# analyzer.net
KiCad netlist of a schematic drawn in EAGLE
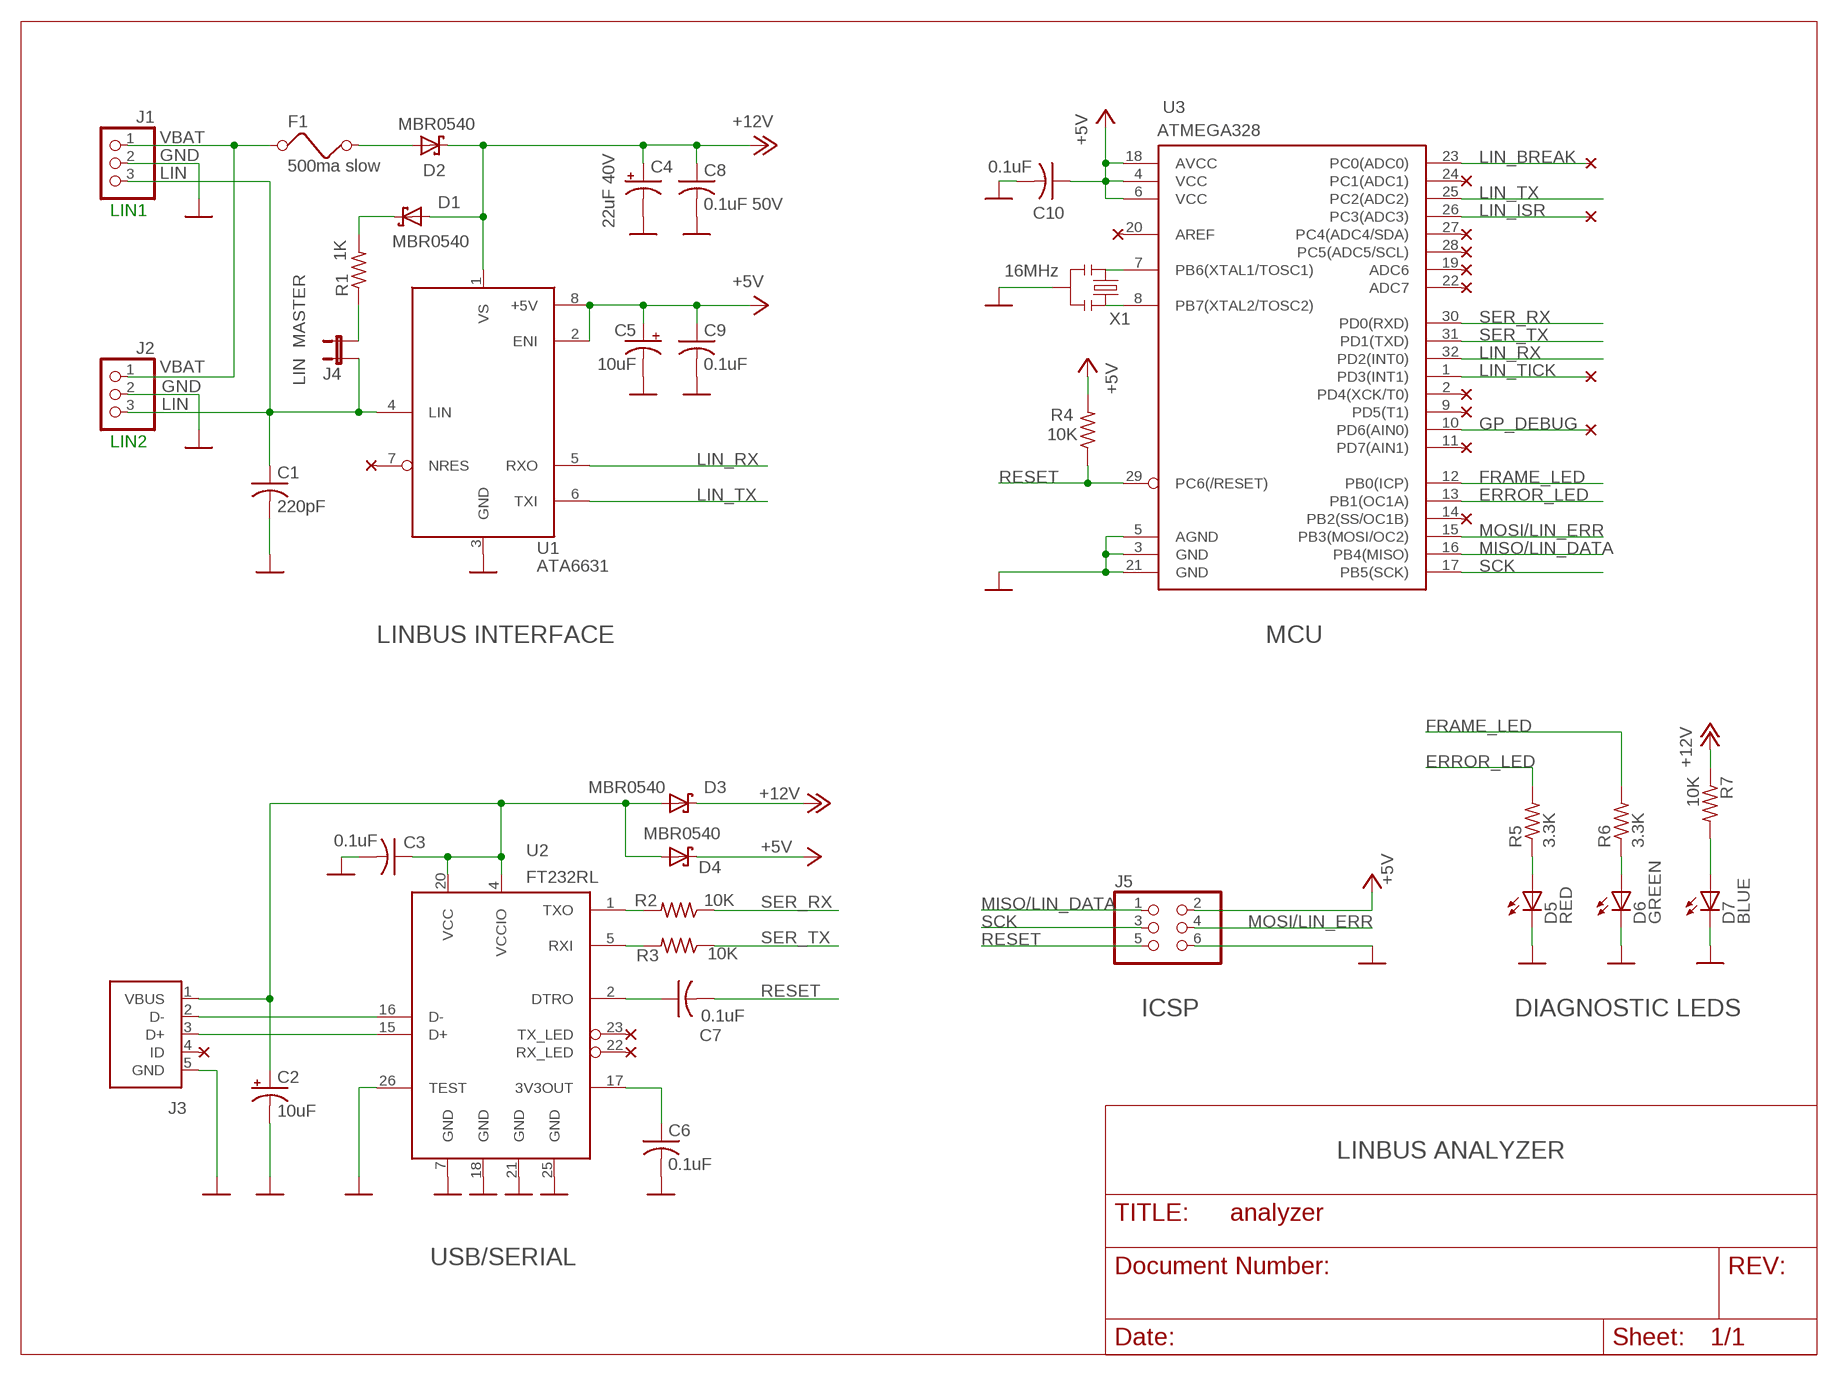
[diagram p0: schematic, sheet 1]

(export (version "E")
  (design (tool "Eeschema 10.0.6"))
  (components
    (comp (ref "C1")
      (value "220pF")
      (footprint "eagle-import:C0805")
      (libsource (lib "eagle-import") (part "C-USC0805"))
    )
    (comp (ref "C2")
      (value "10uF")
      (footprint "eagle-import:A_3216-18R")
      (libsource (lib "eagle-import") (part "CPOL-USA/3216-18R"))
    )
    (comp (ref "C3")
      (value "0.1uF")
      (footprint "eagle-import:C0805")
      (libsource (lib "eagle-import") (part "C-USC0805"))
    )
    (comp (ref "C4")
      (value "22uF 40V")
      (footprint "eagle-import:UD-6,3X5,8_NICHICON")
      (libsource (lib "eagle-import") (part "CPOL-USUD-6,3X5,8"))
    )
    (comp (ref "C5")
      (value "10uF")
      (footprint "eagle-import:A_3216-18R")
      (libsource (lib "eagle-import") (part "CPOL-USA/3216-18R"))
    )
    (comp (ref "C6")
      (value "0.1uF")
      (footprint "eagle-import:C0805")
      (libsource (lib "eagle-import") (part "C-USC0805"))
    )
    (comp (ref "C7")
      (value "0.1uF")
      (footprint "eagle-import:C0805")
      (libsource (lib "eagle-import") (part "C-USC0805"))
    )
    (comp (ref "C8")
      (value "0.1uF 50V")
      (footprint "eagle-import:C0805")
      (libsource (lib "eagle-import") (part "C-USC0805"))
    )
    (comp (ref "C9")
      (value "0.1uF")
      (footprint "eagle-import:C0805")
      (libsource (lib "eagle-import") (part "C-USC0805"))
    )
    (comp (ref "C10")
      (value "0.1uF")
      (footprint "eagle-import:C0805")
      (libsource (lib "eagle-import") (part "C-USC0805"))
    )
    (comp (ref "D1")
      (value "MBR0540")
      (footprint "eagle-import:SOD123FL")
      (libsource (lib "eagle-import") (part "SMF5.0AT1"))
    )
    (comp (ref "D2")
      (value "MBR0540")
      (footprint "eagle-import:SOD123FL")
      (libsource (lib "eagle-import") (part "SMF5.0AT1"))
    )
    (comp (ref "D3")
      (value "MBR0540")
      (footprint "eagle-import:SOD123FL")
      (libsource (lib "eagle-import") (part "SMF5.0AT1"))
    )
    (comp (ref "D4")
      (value "MBR0540")
      (footprint "eagle-import:SOD123FL")
      (libsource (lib "eagle-import") (part "SMF5.0AT1"))
    )
    (comp (ref "D5")
      (value "RED")
      (footprint "eagle-import:1206-LED")
      (libsource (lib "eagle-import") (part "LED"))
    )
    (comp (ref "D6")
      (value "GREEN")
      (footprint "eagle-import:1206-LED")
      (libsource (lib "eagle-import") (part "LED"))
    )
    (comp (ref "D7")
      (value "BLUE")
      (footprint "eagle-import:1206-LED")
      (libsource (lib "eagle-import") (part "LED"))
    )
    (comp (ref "F1")
      (value "500ma slow")
      (footprint "eagle-import:1206")
      (libsource (lib "eagle-import") (part "FUSE"))
    )
    (comp (ref "J1")
      (value "PINHD-1X3")
      (footprint "eagle-import:1X03")
      (libsource (lib "eagle-import") (part "PINHD-1X3"))
    )
    (comp (ref "J2")
      (value "PINHD-1X3")
      (footprint "eagle-import:1X03")
      (libsource (lib "eagle-import") (part "PINHD-1X3"))
    )
    (comp (ref "J3")
      (value "USBSMD")
      (footprint "eagle-import:USB-MINIB")
      (libsource (lib "eagle-import") (part "USBSMD"))
    )
    (comp (ref "J4")
      (value "JP1E")
      (footprint "eagle-import:JP1")
      (libsource (lib "eagle-import") (part "JP1E"))
    )
    (comp (ref "J5")
      (value "PINHD-2X3")
      (footprint "eagle-import:2X03")
      (libsource (lib "eagle-import") (part "PINHD-2X3"))
    )
    (comp (ref "R1")
      (value "1K")
      (footprint "eagle-import:R0805")
      (libsource (lib "eagle-import") (part "R-US_R0805"))
    )
    (comp (ref "R2")
      (value "10K")
      (footprint "eagle-import:R0805")
      (libsource (lib "eagle-import") (part "R-US_R0805"))
    )
    (comp (ref "R3")
      (value "10K")
      (footprint "eagle-import:R0805")
      (libsource (lib "eagle-import") (part "R-US_R0805"))
    )
    (comp (ref "R4")
      (value "10K")
      (footprint "eagle-import:R0805")
      (libsource (lib "eagle-import") (part "R-US_R0805"))
    )
    (comp (ref "R5")
      (value "3.3K")
      (footprint "eagle-import:R0805")
      (libsource (lib "eagle-import") (part "R-US_R0805"))
    )
    (comp (ref "R6")
      (value "3.3K")
      (footprint "eagle-import:R0805")
      (libsource (lib "eagle-import") (part "R-US_R0805"))
    )
    (comp (ref "R7")
      (value "10K")
      (footprint "eagle-import:R0805")
      (libsource (lib "eagle-import") (part "R-US_R0805"))
    )
    (comp (ref "U1")
      (value "ATA6631")
      (footprint "eagle-import:SO-08")
      (libsource (lib "eagle-import") (part "ATA6631"))
    )
    (comp (ref "U2")
      (value "FT232RL")
      (footprint "eagle-import:SSOP28DB")
      (libsource (lib "eagle-import") (part "FT232RL"))
    )
    (comp (ref "U3")
      (value "ATMEGA328")
      (footprint "eagle-import:TQFP32-08")
      (libsource (lib "eagle-import") (part "ATMEGA328"))
    )
    (comp (ref "X1")
      (value "16MHz")
      (footprint "eagle-import:RESONATOR-SMD")
      (libsource (lib "eagle-import") (part "RESONATORSMD"))
    )
  )
  (nets
    (net (code "1") (name "+5V") (class "Default")
      (node (ref "C10") (pin "1") (pinfunction "1_1") (pintype "passive"))
      (node (ref "C5") (pin "+") (pinfunction "+_+") (pintype "passive"))
      (node (ref "C9") (pin "1") (pinfunction "1_1") (pintype "passive"))
      (node (ref "D4") (pin "C") (pinfunction "C_C") (pintype "passive"))
      (node (ref "J5") (pin "2") (pinfunction "2_2") (pintype "passive"))
      (node (ref "R4") (pin "2") (pinfunction "2_2") (pintype "passive"))
      (node (ref "U1") (pin "2") (pinfunction "ENI_2") (pintype "input"))
      (node (ref "U1") (pin "8") (pinfunction "+5V_8") (pintype "power_in"))
      (node (ref "U3") (pin "18") (pinfunction "AVCC_18") (pintype "power_in"))
      (node (ref "U3") (pin "4") (pinfunction "VCC_4") (pintype "power_in"))
      (node (ref "U3") (pin "6") (pinfunction "VCC_6") (pintype "power_in"))
    )
    (net (code "2") (name "+12V") (class "Default")
      (node (ref "C4") (pin "+") (pinfunction "+_+") (pintype "passive"))
      (node (ref "C8") (pin "1") (pinfunction "1_1") (pintype "passive"))
      (node (ref "D1") (pin "A") (pinfunction "A_A") (pintype "passive"))
      (node (ref "D2") (pin "C") (pinfunction "C_C") (pintype "passive"))
      (node (ref "D3") (pin "C") (pinfunction "C_C") (pintype "passive"))
      (node (ref "R7") (pin "1") (pinfunction "1_1") (pintype "passive"))
      (node (ref "U1") (pin "1") (pinfunction "VS_1") (pintype "power_in"))
    )
    (net (code "3") (name "/AREF") (class "Default")
      (node (ref "U3") (pin "20") (pinfunction "AREF_20") (pintype "power_in"))
    )
    (net (code "4") (name "/ERROR_LED") (class "Default")
      (node (ref "R5") (pin "2") (pinfunction "2_2") (pintype "passive"))
      (node (ref "U3") (pin "13") (pinfunction "PB1(OC1A)_13") (pintype "bidirectional"))
    )
    (net (code "5") (name "/FRAME_LED") (class "Default")
      (node (ref "R6") (pin "2") (pinfunction "2_2") (pintype "passive"))
      (node (ref "U3") (pin "12") (pinfunction "PB0(ICP)_12") (pintype "bidirectional"))
    )
    (net (code "6") (name "/GP_DEBUG") (class "Default")
      (node (ref "U3") (pin "10") (pinfunction "PD6(AIN0)_10") (pintype "bidirectional"))
    )
    (net (code "7") (name "/LIN") (class "Default")
      (node (ref "C1") (pin "1") (pinfunction "1_1") (pintype "passive"))
      (node (ref "J1") (pin "3") (pinfunction "3_3") (pintype "passive"))
      (node (ref "J2") (pin "3") (pinfunction "3_3") (pintype "passive"))
      (node (ref "J4") (pin "1") (pinfunction "1_1") (pintype "passive"))
      (node (ref "U1") (pin "4") (pinfunction "LIN_4") (pintype "bidirectional"))
    )
    (net (code "8") (name "/LIN_BREAK") (class "Default")
      (node (ref "U3") (pin "23") (pinfunction "PC0(ADC0)_23") (pintype "bidirectional"))
    )
    (net (code "9") (name "/LIN_ISR") (class "Default")
      (node (ref "U3") (pin "26") (pinfunction "PC3(ADC3)_26") (pintype "bidirectional"))
    )
    (net (code "10") (name "/LIN_RX") (class "Default")
      (node (ref "U1") (pin "5") (pinfunction "RXO_5") (pintype "output"))
      (node (ref "U3") (pin "32") (pinfunction "PD2(INT0)_32") (pintype "bidirectional"))
    )
    (net (code "11") (name "/LIN_TICK") (class "Default")
      (node (ref "U3") (pin "1") (pinfunction "PD3(INT1)_1") (pintype "bidirectional"))
    )
    (net (code "12") (name "/LIN_TX") (class "Default")
      (node (ref "U1") (pin "6") (pinfunction "TXI_6") (pintype "input"))
      (node (ref "U3") (pin "25") (pinfunction "PC2(ADC2)_25") (pintype "bidirectional"))
    )
    (net (code "13") (name "/MISO{slash}LIN_DATA") (class "Default")
      (node (ref "J5") (pin "1") (pinfunction "1_1") (pintype "passive"))
      (node (ref "U3") (pin "16") (pinfunction "PB4(MISO)_16") (pintype "bidirectional"))
    )
    (net (code "14") (name "/MOSI{slash}LIN_ERR") (class "Default")
      (node (ref "J5") (pin "4") (pinfunction "4_4") (pintype "passive"))
      (node (ref "U3") (pin "15") (pinfunction "PB3(MOSI/OC2)_15") (pintype "bidirectional"))
    )
    (net (code "15") (name "/RESET") (class "Default")
      (node (ref "C7") (pin "2") (pinfunction "2_2") (pintype "passive"))
      (node (ref "J5") (pin "5") (pinfunction "5_5") (pintype "passive"))
      (node (ref "R4") (pin "1") (pinfunction "1_1") (pintype "passive"))
      (node (ref "U3") (pin "29") (pinfunction "PC6(/RESET)_29") (pintype "bidirectional"))
    )
    (net (code "16") (name "/SCK") (class "Default")
      (node (ref "J5") (pin "3") (pinfunction "3_3") (pintype "passive"))
      (node (ref "U3") (pin "17") (pinfunction "PB5(SCK)_17") (pintype "bidirectional"))
    )
    (net (code "17") (name "/SER_RX") (class "Default")
      (node (ref "R2") (pin "1") (pinfunction "1_1") (pintype "passive"))
      (node (ref "U3") (pin "30") (pinfunction "PD0(RXD)_30") (pintype "bidirectional"))
    )
    (net (code "18") (name "/SER_TX") (class "Default")
      (node (ref "R3") (pin "1") (pinfunction "1_1") (pintype "passive"))
      (node (ref "U3") (pin "31") (pinfunction "PD1(TXD)_31") (pintype "bidirectional"))
    )
    (net (code "19") (name "/VBAT") (class "Default")
      (node (ref "F1") (pin "1") (pinfunction "1_1") (pintype "passive"))
      (node (ref "J1") (pin "1") (pinfunction "1_1") (pintype "passive"))
      (node (ref "J2") (pin "1") (pinfunction "1_1") (pintype "passive"))
    )
    (net (code "20") (name "GND") (class "Default")
      (node (ref "C1") (pin "2") (pinfunction "2_2") (pintype "passive"))
      (node (ref "C10") (pin "2") (pinfunction "2_2") (pintype "passive"))
      (node (ref "C2") (pin "-") (pinfunction "-_-") (pintype "passive"))
      (node (ref "C3") (pin "2") (pinfunction "2_2") (pintype "passive"))
      (node (ref "C4") (pin "-") (pinfunction "-_-") (pintype "passive"))
      (node (ref "C5") (pin "-") (pinfunction "-_-") (pintype "passive"))
      (node (ref "C6") (pin "2") (pinfunction "2_2") (pintype "passive"))
      (node (ref "C8") (pin "2") (pinfunction "2_2") (pintype "passive"))
      (node (ref "C9") (pin "2") (pinfunction "2_2") (pintype "passive"))
      (node (ref "D5") (pin "C") (pinfunction "C_C") (pintype "passive"))
      (node (ref "D6") (pin "C") (pinfunction "C_C") (pintype "passive"))
      (node (ref "D7") (pin "C") (pinfunction "C_C") (pintype "passive"))
      (node (ref "J1") (pin "2") (pinfunction "2_2") (pintype "passive"))
      (node (ref "J2") (pin "2") (pinfunction "2_2") (pintype "passive"))
      (node (ref "J3") (pin "5") (pinfunction "GND_5") (pintype "bidirectional"))
      (node (ref "J5") (pin "6") (pinfunction "6_6") (pintype "passive"))
      (node (ref "U1") (pin "3") (pinfunction "GND_3") (pintype "power_in"))
      (node (ref "U2") (pin "18") (pinfunction "GND_18") (pintype "power_in"))
      (node (ref "U2") (pin "21") (pinfunction "GND_21") (pintype "power_in"))
      (node (ref "U2") (pin "25") (pinfunction "GND_25") (pintype "power_in"))
      (node (ref "U2") (pin "26") (pinfunction "TEST_26") (pintype "input"))
      (node (ref "U2") (pin "7") (pinfunction "GND_7") (pintype "power_in"))
      (node (ref "U3") (pin "21") (pinfunction "GND_21") (pintype "power_in"))
      (node (ref "U3") (pin "3") (pinfunction "GND_3") (pintype "power_in"))
      (node (ref "U3") (pin "5") (pinfunction "AGND_5") (pintype "power_in"))
      (node (ref "X1") (pin "2") (pinfunction "2_2") (pintype "passive"))
    )
    (net (code "21") (name "Net-(D1-PadC)") (class "Default")
      (node (ref "D1") (pin "C") (pinfunction "C_C") (pintype "passive"))
      (node (ref "R1") (pin "2") (pinfunction "2_2") (pintype "passive"))
    )
    (net (code "22") (name "Net-(D2-PadA)") (class "Default")
      (node (ref "D2") (pin "A") (pinfunction "A_A") (pintype "passive"))
      (node (ref "F1") (pin "2") (pinfunction "2_2") (pintype "passive"))
    )
    (net (code "23") (name "Net-(D5-PadA)") (class "Default")
      (node (ref "D5") (pin "A") (pinfunction "A_A") (pintype "passive"))
      (node (ref "R5") (pin "1") (pinfunction "1_1") (pintype "passive"))
    )
    (net (code "24") (name "Net-(D6-PadA)") (class "Default")
      (node (ref "D6") (pin "A") (pinfunction "A_A") (pintype "passive"))
      (node (ref "R6") (pin "1") (pinfunction "1_1") (pintype "passive"))
    )
    (net (code "25") (name "Net-(D7-PadA)") (class "Default")
      (node (ref "D7") (pin "A") (pinfunction "A_A") (pintype "passive"))
      (node (ref "R7") (pin "2") (pinfunction "2_2") (pintype "passive"))
    )
    (net (code "26") (name "Net-(J3-D+)") (class "Default")
      (node (ref "J3") (pin "3") (pinfunction "D+_3") (pintype "bidirectional"))
      (node (ref "U2") (pin "15") (pinfunction "D+_15") (pintype "passive"))
    )
    (net (code "27") (name "Net-(J3-D-)") (class "Default")
      (node (ref "J3") (pin "2") (pinfunction "D-_2") (pintype "bidirectional"))
      (node (ref "U2") (pin "16") (pinfunction "D-_16") (pintype "passive"))
    )
    (net (code "28") (name "Net-(J3-VBUS)") (class "Default")
      (node (ref "C2") (pin "+") (pinfunction "+_+") (pintype "passive"))
      (node (ref "C3") (pin "1") (pinfunction "1_1") (pintype "passive"))
      (node (ref "D3") (pin "A") (pinfunction "A_A") (pintype "passive"))
      (node (ref "D4") (pin "A") (pinfunction "A_A") (pintype "passive"))
      (node (ref "J3") (pin "1") (pinfunction "VBUS_1") (pintype "bidirectional"))
      (node (ref "U2") (pin "20") (pinfunction "VCC_20") (pintype "power_in"))
      (node (ref "U2") (pin "4") (pinfunction "VCCIO_4") (pintype "power_in"))
    )
    (net (code "29") (name "Net-(J4-Pad2)") (class "Default")
      (node (ref "J4") (pin "2") (pinfunction "2_2") (pintype "passive"))
      (node (ref "R1") (pin "1") (pinfunction "1_1") (pintype "passive"))
    )
    (net (code "30") (name "Net-(U2-3V3OUT)") (class "Default")
      (node (ref "C6") (pin "1") (pinfunction "1_1") (pintype "passive"))
      (node (ref "U2") (pin "17") (pinfunction "3V3OUT_17") (pintype "power_in"))
    )
    (net (code "31") (name "Net-(U2-DTRO)") (class "Default")
      (node (ref "C7") (pin "1") (pinfunction "1_1") (pintype "passive"))
      (node (ref "U2") (pin "2") (pinfunction "DTRO_2") (pintype "output"))
    )
    (net (code "32") (name "Net-(U2-RXI)") (class "Default")
      (node (ref "R3") (pin "2") (pinfunction "2_2") (pintype "passive"))
      (node (ref "U2") (pin "5") (pinfunction "RXI_5") (pintype "input"))
    )
    (net (code "33") (name "Net-(U2-TXO)") (class "Default")
      (node (ref "R2") (pin "2") (pinfunction "2_2") (pintype "passive"))
      (node (ref "U2") (pin "1") (pinfunction "TXO_1") (pintype "output"))
    )
    (net (code "34") (name "Net-(U3-PB6(XTAL1{slash}TOSC1))") (class "Default")
      (node (ref "U3") (pin "7") (pinfunction "PB6(XTAL1/TOSC1)_7") (pintype "bidirectional"))
      (node (ref "X1") (pin "3") (pinfunction "3_3") (pintype "passive"))
    )
    (net (code "35") (name "Net-(U3-PB7(XTAL2{slash}TOSC2))") (class "Default")
      (node (ref "U3") (pin "8") (pinfunction "PB7(XTAL2/TOSC2)_8") (pintype "bidirectional"))
      (node (ref "X1") (pin "1") (pinfunction "1_1") (pintype "passive"))
    )
    (net (code "36") (name "unconnected-(J3-ID-Pad4)") (class "Default")
      (node (ref "J3") (pin "4") (pinfunction "ID_4") (pintype "bidirectional"))
    )
    (net (code "37") (name "unconnected-(U1-NRES-Pad7)") (class "Default")
      (node (ref "U1") (pin "7") (pinfunction "NRES_7") (pintype "output"))
    )
    (net (code "38") (name "unconnected-(U2-RX_LED-Pad22)") (class "Default")
      (node (ref "U2") (pin "22") (pinfunction "RX_LED_22") (pintype "output"))
    )
    (net (code "39") (name "unconnected-(U2-TX_LED-Pad23)") (class "Default")
      (node (ref "U2") (pin "23") (pinfunction "TX_LED_23") (pintype "output"))
    )
    (net (code "40") (name "unconnected-(U3-ADC6-Pad19)") (class "Default")
      (node (ref "U3") (pin "19") (pinfunction "ADC6_19") (pintype "bidirectional"))
    )
    (net (code "41") (name "unconnected-(U3-ADC7-Pad22)") (class "Default")
      (node (ref "U3") (pin "22") (pinfunction "ADC7_22") (pintype "bidirectional"))
    )
    (net (code "42") (name "unconnected-(U3-PB2(SS{slash}OC1B)-Pad14)") (class "Default")
      (node (ref "U3") (pin "14") (pinfunction "PB2(SS/OC1B)_14") (pintype "bidirectional"))
    )
    (net (code "43") (name "unconnected-(U3-PC1(ADC1)-Pad24)") (class "Default")
      (node (ref "U3") (pin "24") (pinfunction "PC1(ADC1)_24") (pintype "bidirectional"))
    )
    (net (code "44") (name "unconnected-(U3-PC4(ADC4{slash}SDA)-Pad27)") (class "Default")
      (node (ref "U3") (pin "27") (pinfunction "PC4(ADC4/SDA)_27") (pintype "bidirectional"))
    )
    (net (code "45") (name "unconnected-(U3-PC5(ADC5{slash}SCL)-Pad28)") (class "Default")
      (node (ref "U3") (pin "28") (pinfunction "PC5(ADC5/SCL)_28") (pintype "bidirectional"))
    )
    (net (code "46") (name "unconnected-(U3-PD4(XCK{slash}T0)-Pad2)") (class "Default")
      (node (ref "U3") (pin "2") (pinfunction "PD4(XCK/T0)_2") (pintype "bidirectional"))
    )
    (net (code "47") (name "unconnected-(U3-PD5(T1)-Pad9)") (class "Default")
      (node (ref "U3") (pin "9") (pinfunction "PD5(T1)_9") (pintype "bidirectional"))
    )
    (net (code "48") (name "unconnected-(U3-PD7(AIN1)-Pad11)") (class "Default")
      (node (ref "U3") (pin "11") (pinfunction "PD7(AIN1)_11") (pintype "bidirectional"))
    )
  )
)
